# 5_Motor_Driver.net
KiCad netlist of a schematic drawn in Altium Designer
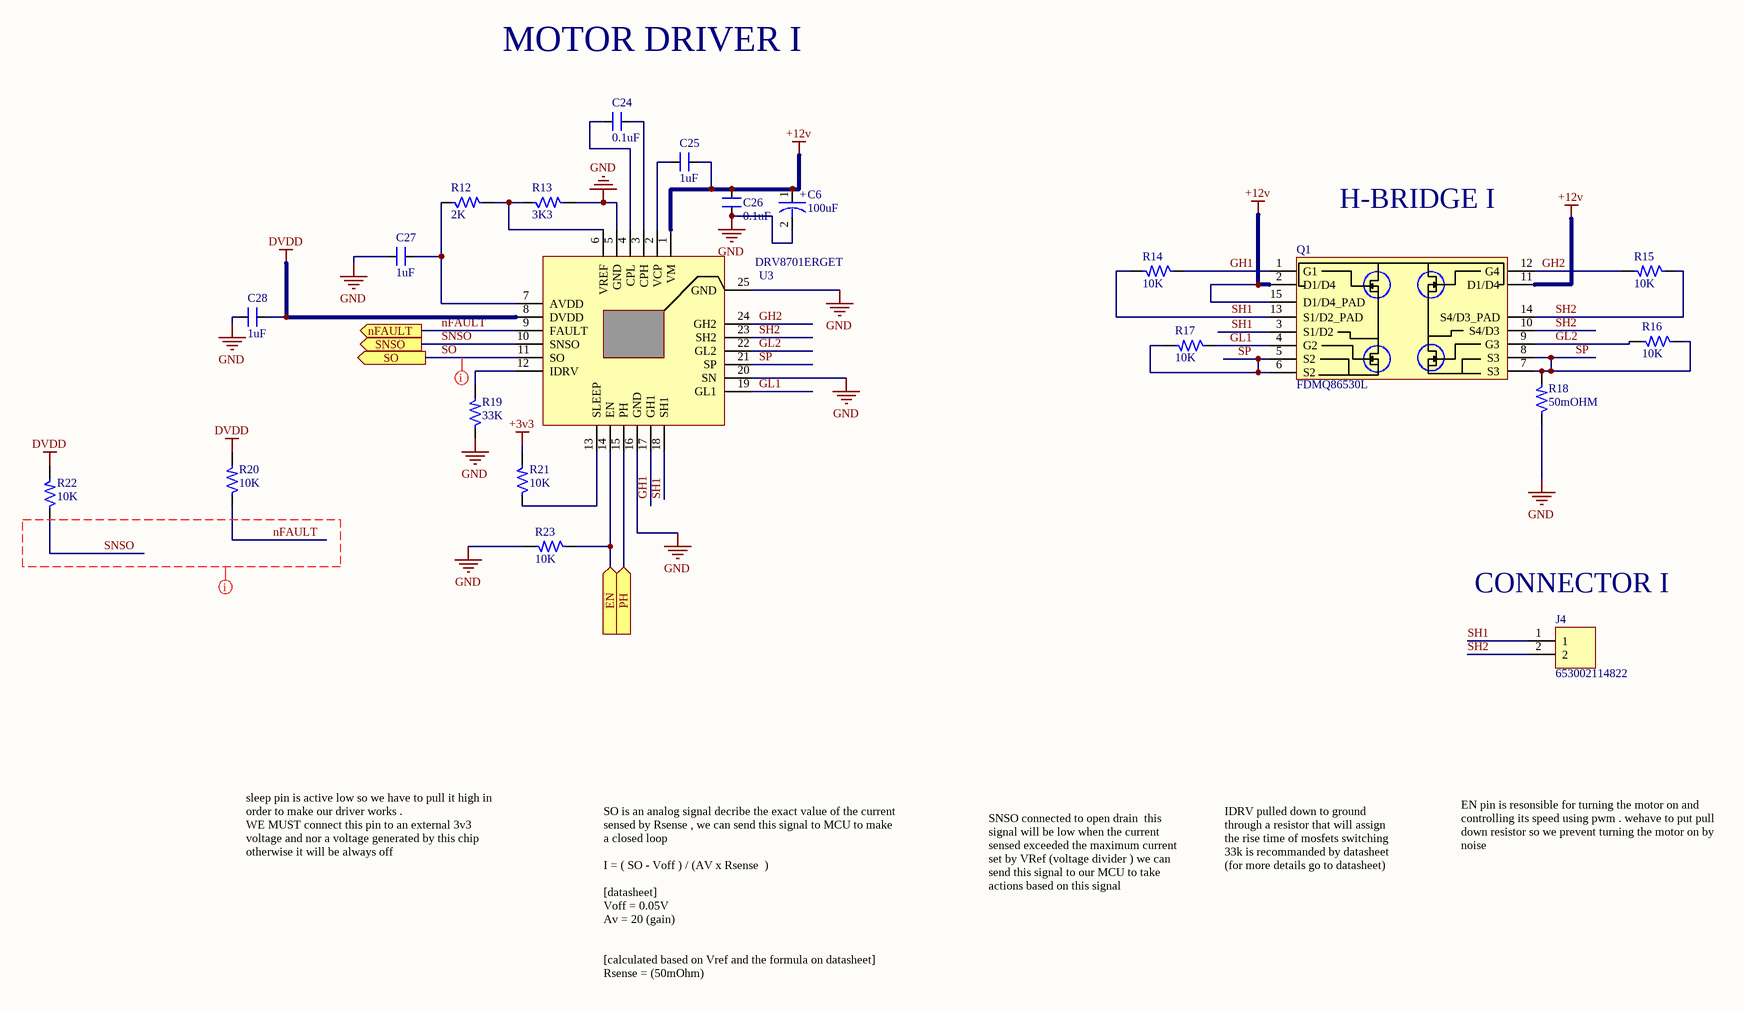
[diagram p0: [5]Motor_Driver.SchDoc]

(export (version "E")
  (design (tool "Eeschema 10.0.6"))
  (components
    (comp (ref "C6")
      (value "100uF")
      (footprint "ACAP_P305_D393_H393_RAD")
      (description "100µF 50V Aluminum Polymer Capacitor Radial, Can - SMD 28mOhm 4000 Hrs @ 125°C")
      (fields
        (field (name "MANUFACTURER") "Nichicon")
        (field (name "MANUFACTURER PART NUMBER") "GYA1H101MCQ1GS")
      )
      (libsource (lib "ESTEEMPCBLIB") (part "CAP-P_100uF-50V-20%-RAD"))
    )
    (comp (ref "C24")
      (value "0.1uF")
      (footprint "CAP_0805")
      (description "0.1µF ±5% 50V Ceramic Capacitor X7R 0805 (2012 Metric)")
      (fields
        (field (name "MANUFACTURER") "AVX Corporation")
        (field (name "MANUFACTURER PART NUMBER") "08055C104JAT4A")
      )
      (libsource (lib "ESTEEMPCBLIB") (part "CAP_0.1uF-50V-5%-0805"))
    )
    (comp (ref "C25")
      (value "1uF")
      (footprint "CAP_0805")
      (description "1µF ±5% 50V Ceramic Capacitor X7R 0805 (2012 Metric)")
      (fields
        (field (name "MANUFACTURER") "Samsung")
        (field (name "MANUFACTURER PART NUMBER") "CC0805JKX7R9BB105")
      )
      (libsource (lib "ESTEEMPCBLIB") (part "CAP_1uF-50V-5%-0805"))
    )
    (comp (ref "C26")
      (value "0.1uF")
      (footprint "CAP_0805")
      (description "0.1µF ±5% 50V Ceramic Capacitor X7R 0805 (2012 Metric)")
      (fields
        (field (name "MANUFACTURER") "AVX Corporation")
        (field (name "MANUFACTURER PART NUMBER") "08055C104JAT4A")
      )
      (libsource (lib "ESTEEMPCBLIB") (part "CAP_0.1uF-50V-5%-0805"))
    )
    (comp (ref "C27")
      (value "1uF")
      (footprint "CAP_0805")
      (description "1µF ±5% 50V Ceramic Capacitor X7R 0805 (2012 Metric)")
      (fields
        (field (name "MANUFACTURER") "Samsung")
        (field (name "MANUFACTURER PART NUMBER") "CC0805JKX7R9BB105")
      )
      (libsource (lib "ESTEEMPCBLIB") (part "CAP_1uF-50V-5%-0805"))
    )
    (comp (ref "C28")
      (value "1uF")
      (footprint "CAP_0805")
      (description "1µF ±5% 50V Ceramic Capacitor X7R 0805 (2012 Metric)")
      (fields
        (field (name "MANUFACTURER") "Samsung")
        (field (name "MANUFACTURER PART NUMBER") "CC0805JKX7R9BB105")
      )
      (libsource (lib "ESTEEMPCBLIB") (part "CAP_1uF-50V-5%-0805"))
    )
    (comp (ref "J4")
      (value "653002114822")
      (footprint "CON2_50_653002114822_TH_ST")
      (description "2 Pins, 1 Row 1.25mm Pitch, Straight Connector, male")
      (fields (field (name "MANUFACTURER") "JST") (field (name "MATING PART NUMBER") "653002113322"))
      (libsource (lib "ESTEEMPCBLIB") (part "CON-PLG_2X1-50-ST-TH"))
    )
    (comp (ref "Q1")
      (value "FDMQ86530L")
      (footprint "DFN5045-12_33_212_27X15_SMD_1")
      (description "Mosfet Array 4 N-Channel 8A (Ta) Surface Mount V-DFN5045-12")
      (fields (field (name "MANUFACTURER") "ON Semiconductor"))
      (libsource (lib "ESTEEMPCBLIB") (part "MOSFET-N_60V-8A-V-DFN5045-12"))
    )
    (comp (ref "R12")
      (value "2K")
      (footprint "RES_0805")
      (description "2 kOhms ±1% 0.125W, 1/8W Chip Resistor 0805 (2012 Metric) Moisture Resistant Thick Film")
      (fields
        (field (name "MANUFACTURER") "TE Connectivity")
        (field (name "MANUFACTURER PART NUMBER") "RC0805FR-072KL")
      )
      (libsource (lib "ESTEEMPCBLIB") (part "RES_2K-0.125W-1%-0805"))
    )
    (comp (ref "R13")
      (value "3K3")
      (footprint "RES_0603")
      (description "3.3 kOhms ±1% 0.1W, 1/10W Chip Resistor 0603 (1608 Metric) Automotive AEC-Q200 Thick Film")
      (fields (field (name "MANUFACTURER") "Wilson") (field (name "MANUFACTURER PART NUMBER") "WR06X3301FTL"))
      (libsource (lib "ESTEEMPCBLIB") (part "RES_3.3K-0.1W-1%-0603"))
    )
    (comp (ref "R14")
      (value "10K")
      (footprint "RES_0805")
      (description "10 kOhms ±1% 0.125W, 1/8W Chip Resistor 0805 (2012 Metric) Automotive AEC-Q200 Thick Film")
      (fields (field (name "MANUFACTURER") "CTS") (field (name "MANUFACTURER PART NUMBER") "WR08X1002FTL"))
      (libsource (lib "ESTEEMPCBLIB") (part "RES_10K-0.125W-1%-0805"))
    )
    (comp (ref "R15")
      (value "10K")
      (footprint "RES_0805")
      (description "10 kOhms ±1% 0.125W, 1/8W Chip Resistor 0805 (2012 Metric) Automotive AEC-Q200 Thick Film")
      (fields (field (name "MANUFACTURER") "CTS") (field (name "MANUFACTURER PART NUMBER") "WR08X1002FTL"))
      (libsource (lib "ESTEEMPCBLIB") (part "RES_10K-0.125W-1%-0805"))
    )
    (comp (ref "R16")
      (value "10K")
      (footprint "RES_0805")
      (description "10 kOhms ±1% 0.125W, 1/8W Chip Resistor 0805 (2012 Metric) Automotive AEC-Q200 Thick Film")
      (fields (field (name "MANUFACTURER") "CTS") (field (name "MANUFACTURER PART NUMBER") "WR08X1002FTL"))
      (libsource (lib "ESTEEMPCBLIB") (part "RES_10K-0.125W-1%-0805"))
    )
    (comp (ref "R17")
      (value "10K")
      (footprint "RES_0805")
      (description "10 kOhms ±1% 0.125W, 1/8W Chip Resistor 0805 (2012 Metric) Automotive AEC-Q200 Thick Film")
      (fields (field (name "MANUFACTURER") "CTS") (field (name "MANUFACTURER PART NUMBER") "WR08X1002FTL"))
      (libsource (lib "ESTEEMPCBLIB") (part "RES_10K-0.125W-1%-0805"))
    )
    (comp (ref "R18")
      (value "50mOHM")
      (footprint "RES_2512")
      (fields
        (field (name "MANUFACTURER") "Yageo")
        (field (name "MANUFACTURER PART NUMBER") "PA2512FKF7W0R05E")
      )
      (libsource (lib "ESTEEMPCBLIB") (part "RES_50mOhm-2W-1%-2512"))
    )
    (comp (ref "R19")
      (value "33K")
      (footprint "RES_0805")
      (fields
        (field (name "MANUFACTURER") "Vishay BCcomponents")
        (field (name "MANUFACTURER PART NUMBER") "CRG0805F33K")
      )
      (libsource (lib "ESTEEMPCBLIB") (part "RES_33K-0.125W-1%-0805"))
    )
    (comp (ref "R20")
      (value "10K")
      (footprint "RES_0805")
      (description "10 kOhms ±1% 0.125W, 1/8W Chip Resistor 0805 (2012 Metric) Automotive AEC-Q200 Thick Film")
      (fields (field (name "MANUFACTURER") "CTS") (field (name "MANUFACTURER PART NUMBER") "WR08X1002FTL"))
      (libsource (lib "ESTEEMPCBLIB") (part "RES_10K-0.125W-1%-0805"))
    )
    (comp (ref "R21")
      (value "10K")
      (footprint "RES_0805")
      (description "10 kOhms ±1% 0.125W, 1/8W Chip Resistor 0805 (2012 Metric) Automotive AEC-Q200 Thick Film")
      (fields (field (name "MANUFACTURER") "CTS") (field (name "MANUFACTURER PART NUMBER") "WR08X1002FTL"))
      (libsource (lib "ESTEEMPCBLIB") (part "RES_10K-0.125W-1%-0805"))
    )
    (comp (ref "R22")
      (value "10K")
      (footprint "RES_0805")
      (description "10 kOhms ±1% 0.125W, 1/8W Chip Resistor 0805 (2012 Metric) Automotive AEC-Q200 Thick Film")
      (fields (field (name "MANUFACTURER") "CTS") (field (name "MANUFACTURER PART NUMBER") "WR08X1002FTL"))
      (libsource (lib "ESTEEMPCBLIB") (part "RES_10K-0.125W-1%-0805"))
    )
    (comp (ref "R23")
      (value "10K")
      (footprint "RES_0805")
      (description "10 kOhms ±1% 0.125W, 1/8W Chip Resistor 0805 (2012 Metric) Automotive AEC-Q200 Thick Film")
      (fields (field (name "MANUFACTURER") "CTS") (field (name "MANUFACTURER PART NUMBER") "WR08X1002FTL"))
      (libsource (lib "ESTEEMPCBLIB") (part "RES_10K-0.125W-1%-0805"))
    )
    (comp (ref "U3")
      (value "DRV8701ERGET")
      (footprint "VFQFN24_19.6_196_12X32_SMD_1")
      (description "Motor Driver Power MOSFET Parallel 24-VQFN (4x4)")
      (fields (field (name "MANUFACTURER") "Texas Instruments"))
      (libsource (lib "ESTEEMPCBLIB") (part "IC_DRV8701ERGET"))
    )
  )
  (nets
    (net (code "1") (name "+3v3") (class "Default")
      (node (ref "R21") (pin "2") (pinfunction "2_2") (pintype "passive"))
    )
    (net (code "2") (name "+12v") (class "Default")
      (node (ref "C25") (pin "2") (pinfunction "2_2") (pintype "passive"))
      (node (ref "C26") (pin "2") (pinfunction "2_2") (pintype "passive"))
      (node (ref "C6") (pin "1") (pinfunction "1_1") (pintype "passive"))
      (node (ref "Q1") (pin "11") (pinfunction "D1/D4_11") (pintype "passive"))
      (node (ref "Q1") (pin "15") (pinfunction "D1/D4_PAD_15") (pintype "passive"))
      (node (ref "Q1") (pin "2") (pinfunction "D1/D4_2") (pintype "passive"))
      (node (ref "U3") (pin "1") (pinfunction "VM_1") (pintype "passive"))
    )
    (net (code "3") (name "/EN") (class "Default")
      (node (ref "R23") (pin "1") (pinfunction "1_1") (pintype "passive"))
      (node (ref "U3") (pin "14") (pinfunction "EN_14") (pintype "passive"))
    )
    (net (code "4") (name "/GH1") (class "Default")
      (node (ref "Q1") (pin "1") (pinfunction "G1_1") (pintype "passive"))
      (node (ref "R14") (pin "1") (pinfunction "1_1") (pintype "passive"))
      (node (ref "U3") (pin "17") (pinfunction "GH1_17") (pintype "passive"))
    )
    (net (code "5") (name "/GH2") (class "Default")
      (node (ref "Q1") (pin "12") (pinfunction "G4_12") (pintype "passive"))
      (node (ref "R15") (pin "2") (pinfunction "2_2") (pintype "passive"))
      (node (ref "U3") (pin "24") (pinfunction "GH2_24") (pintype "passive"))
    )
    (net (code "6") (name "/GL1") (class "Default")
      (node (ref "Q1") (pin "4") (pinfunction "G2_4") (pintype "passive"))
      (node (ref "R17") (pin "1") (pinfunction "1_1") (pintype "passive"))
      (node (ref "U3") (pin "19") (pinfunction "GL1_19") (pintype "passive"))
    )
    (net (code "7") (name "/GL2") (class "Default")
      (node (ref "Q1") (pin "9") (pinfunction "G3_9") (pintype "passive"))
      (node (ref "R16") (pin "2") (pinfunction "2_2") (pintype "passive"))
      (node (ref "U3") (pin "22") (pinfunction "GL2_22") (pintype "passive"))
    )
    (net (code "8") (name "/PH") (class "Default")
      (node (ref "U3") (pin "15") (pinfunction "PH_15") (pintype "passive"))
    )
    (net (code "9") (name "/SH1") (class "Default")
      (node (ref "J4") (pin "1") (pinfunction "1_1") (pintype "passive"))
      (node (ref "Q1") (pin "13") (pinfunction "S1/D2_PAD_13") (pintype "passive"))
      (node (ref "Q1") (pin "3") (pinfunction "S1/D2_3") (pintype "passive"))
      (node (ref "R14") (pin "2") (pinfunction "2_2") (pintype "passive"))
      (node (ref "U3") (pin "18") (pinfunction "SH1_18") (pintype "passive"))
    )
    (net (code "10") (name "/SH2") (class "Default")
      (node (ref "J4") (pin "2") (pinfunction "2_2") (pintype "passive"))
      (node (ref "Q1") (pin "10") (pinfunction "S4/D3_10") (pintype "passive"))
      (node (ref "Q1") (pin "14") (pinfunction "S4/D3_PAD_14") (pintype "passive"))
      (node (ref "R15") (pin "1") (pinfunction "1_1") (pintype "passive"))
      (node (ref "U3") (pin "23") (pinfunction "SH2_23") (pintype "passive"))
    )
    (net (code "11") (name "/SNSO") (class "Default")
      (node (ref "R22") (pin "1") (pinfunction "1_1") (pintype "passive"))
      (node (ref "U3") (pin "10") (pinfunction "SNSO_10") (pintype "passive"))
    )
    (net (code "12") (name "/SO") (class "Default")
      (node (ref "U3") (pin "11") (pinfunction "SO_11") (pintype "passive"))
    )
    (net (code "13") (name "/SP") (class "Default")
      (node (ref "Q1") (pin "5") (pinfunction "S2_5") (pintype "passive"))
      (node (ref "Q1") (pin "6") (pinfunction "S2_6") (pintype "passive"))
      (node (ref "Q1") (pin "7") (pinfunction "S3_7") (pintype "passive"))
      (node (ref "Q1") (pin "8") (pinfunction "S3_8") (pintype "passive"))
      (node (ref "R16") (pin "1") (pinfunction "1_1") (pintype "passive"))
      (node (ref "R17") (pin "2") (pinfunction "2_2") (pintype "passive"))
      (node (ref "R18") (pin "2") (pinfunction "2_2") (pintype "passive"))
      (node (ref "U3") (pin "21") (pinfunction "SP_21") (pintype "passive"))
    )
    (net (code "14") (name "/nFAULT") (class "Default")
      (node (ref "R20") (pin "1") (pinfunction "1_1") (pintype "passive"))
      (node (ref "U3") (pin "9") (pinfunction "FAULT_9") (pintype "passive"))
    )
    (net (code "15") (name "DVDD") (class "Default")
      (node (ref "C28") (pin "2") (pinfunction "2_2") (pintype "passive"))
      (node (ref "R20") (pin "2") (pinfunction "2_2") (pintype "passive"))
      (node (ref "R22") (pin "2") (pinfunction "2_2") (pintype "passive"))
      (node (ref "U3") (pin "8") (pinfunction "DVDD_8") (pintype "passive"))
    )
    (net (code "16") (name "GND") (class "Default")
      (node (ref "C26") (pin "1") (pinfunction "1_1") (pintype "passive"))
      (node (ref "C27") (pin "1") (pinfunction "1_1") (pintype "passive"))
      (node (ref "C28") (pin "1") (pinfunction "1_1") (pintype "passive"))
      (node (ref "C6") (pin "2") (pinfunction "2_2") (pintype "passive"))
      (node (ref "R13") (pin "2") (pinfunction "2_2") (pintype "passive"))
      (node (ref "R18") (pin "1") (pinfunction "1_1") (pintype "passive"))
      (node (ref "R19") (pin "1") (pinfunction "1_1") (pintype "passive"))
      (node (ref "R23") (pin "2") (pinfunction "2_2") (pintype "passive"))
      (node (ref "U3") (pin "16") (pinfunction "GND_16") (pintype "passive"))
      (node (ref "U3") (pin "20") (pinfunction "SN_20") (pintype "passive"))
      (node (ref "U3") (pin "25") (pinfunction "GND_25") (pintype "passive"))
      (node (ref "U3") (pin "5") (pinfunction "GND_5") (pintype "passive"))
    )
    (net (code "17") (name "Net-(U3-AVDD)") (class "Default")
      (node (ref "C27") (pin "2") (pinfunction "2_2") (pintype "passive"))
      (node (ref "R12") (pin "1") (pinfunction "1_1") (pintype "passive"))
      (node (ref "U3") (pin "7") (pinfunction "AVDD_7") (pintype "passive"))
    )
    (net (code "18") (name "Net-(U3-CPH)") (class "Default")
      (node (ref "C24") (pin "2") (pinfunction "2_2") (pintype "passive"))
      (node (ref "U3") (pin "3") (pinfunction "CPH_3") (pintype "passive"))
    )
    (net (code "19") (name "Net-(U3-CPL)") (class "Default")
      (node (ref "C24") (pin "1") (pinfunction "1_1") (pintype "passive"))
      (node (ref "U3") (pin "4") (pinfunction "CPL_4") (pintype "passive"))
    )
    (net (code "20") (name "Net-(U3-IDRV)") (class "Default")
      (node (ref "R19") (pin "2") (pinfunction "2_2") (pintype "passive"))
      (node (ref "U3") (pin "12") (pinfunction "IDRV_12") (pintype "passive"))
    )
    (net (code "21") (name "Net-(U3-SLEEP)") (class "Default")
      (node (ref "R21") (pin "1") (pinfunction "1_1") (pintype "passive"))
      (node (ref "U3") (pin "13") (pinfunction "SLEEP_13") (pintype "passive"))
    )
    (net (code "22") (name "Net-(U3-VCP)") (class "Default")
      (node (ref "C25") (pin "1") (pinfunction "1_1") (pintype "passive"))
      (node (ref "U3") (pin "2") (pinfunction "VCP_2") (pintype "passive"))
    )
    (net (code "23") (name "Net-(U3-VREF)") (class "Default")
      (node (ref "R12") (pin "2") (pinfunction "2_2") (pintype "passive"))
      (node (ref "R13") (pin "1") (pinfunction "1_1") (pintype "passive"))
      (node (ref "U3") (pin "6") (pinfunction "VREF_6") (pintype "passive"))
    )
  )
)
